# MAX-M8_Breakout.net
KiCad netlist of a schematic drawn in EAGLE
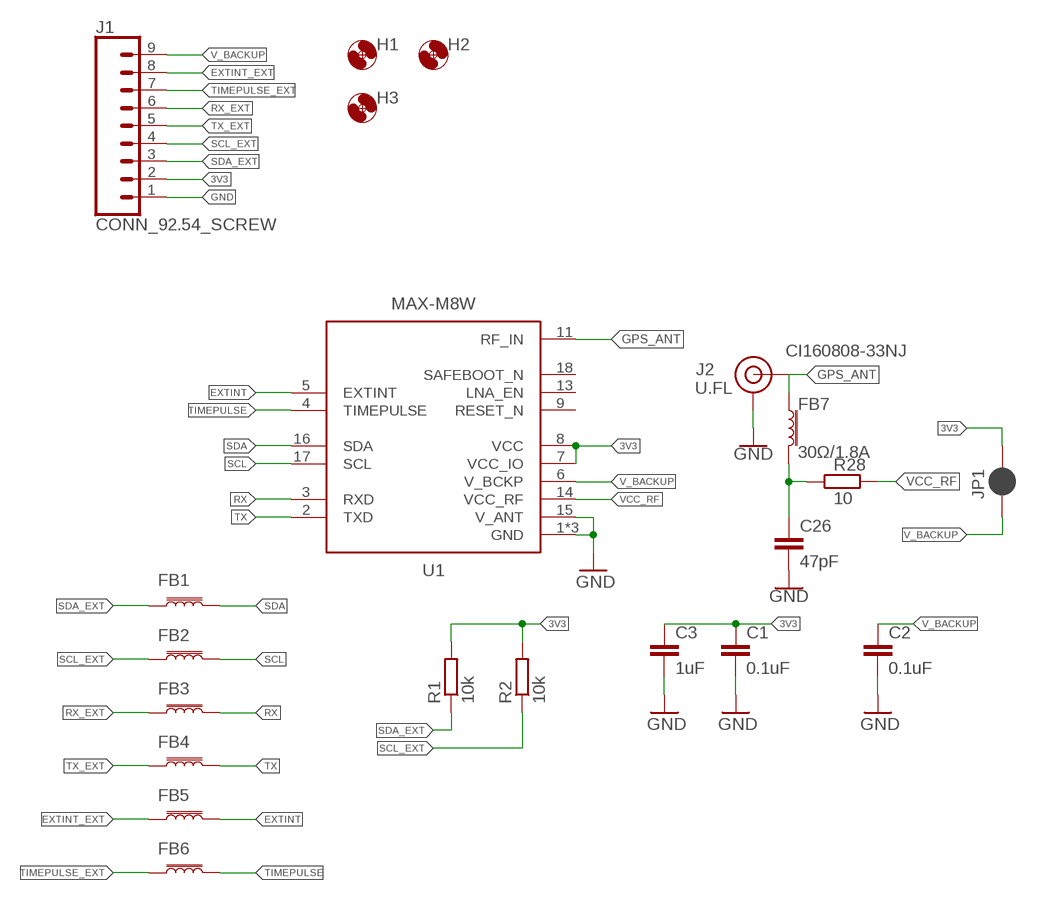
[diagram p0: schematic, sheet 1]

(export (version "E")
  (design (tool "Eeschema 10.0.6"))
  (components
    (comp (ref "C1")
      (value "0.1uF")
      (footprint "eagle-import:C0603")
      (fields (field (name "MF") "Murata") (field (name "MPN") "GCM188R71E104KA57D"))
      (libsource (lib "eagle-import") (part "C-EUC06030.1UF"))
    )
    (comp (ref "C2")
      (value "0.1uF")
      (footprint "eagle-import:C0603")
      (fields (field (name "MF") "Murata") (field (name "MPN") "GCM188R71E104KA57D"))
      (libsource (lib "eagle-import") (part "C-EUC06030.1UF"))
    )
    (comp (ref "C3")
      (value "1uF")
      (footprint "eagle-import:C0603")
      (fields (field (name "MF") "Yaiyo Yuden") (field (name "MPN") "EMK107BJ105KA-T"))
      (libsource (lib "eagle-import") (part "C-EUC06031UF"))
    )
    (comp (ref "C26")
      (value "47pF")
      (footprint "eagle-import:C0402")
      (libsource (lib "eagle-import") (part "C-EUC0402"))
    )
    (comp (ref "FB1")
      (value "FERRITE_BEAD1KS0402")
      (footprint "eagle-import:R0402")
      (fields (field (name "MF") "Murata") (field (name "MPN") "BLM15HD102SN1D"))
      (libsource (lib "eagle-import") (part "FERRITE_BEAD04021KS"))
    )
    (comp (ref "FB2")
      (value "FERRITE_BEAD1KS0402")
      (footprint "eagle-import:R0402")
      (fields (field (name "MF") "Murata") (field (name "MPN") "BLM15HD102SN1D"))
      (libsource (lib "eagle-import") (part "FERRITE_BEAD04021KS"))
    )
    (comp (ref "FB3")
      (value "FERRITE_BEAD1KS0402")
      (footprint "eagle-import:R0402")
      (fields (field (name "MF") "Murata") (field (name "MPN") "BLM15HD102SN1D"))
      (libsource (lib "eagle-import") (part "FERRITE_BEAD04021KS"))
    )
    (comp (ref "FB4")
      (value "FERRITE_BEAD1KS0402")
      (footprint "eagle-import:R0402")
      (fields (field (name "MF") "Murata") (field (name "MPN") "BLM15HD102SN1D"))
      (libsource (lib "eagle-import") (part "FERRITE_BEAD04021KS"))
    )
    (comp (ref "FB5")
      (value "FERRITE_BEAD1KS0402")
      (footprint "eagle-import:R0402")
      (fields (field (name "MF") "Murata") (field (name "MPN") "BLM15HD102SN1D"))
      (libsource (lib "eagle-import") (part "FERRITE_BEAD04021KS"))
    )
    (comp (ref "FB6")
      (value "FERRITE_BEAD1KS0402")
      (footprint "eagle-import:R0402")
      (fields (field (name "MF") "Murata") (field (name "MPN") "BLM15HD102SN1D"))
      (libsource (lib "eagle-import") (part "FERRITE_BEAD04021KS"))
    )
    (comp (ref "FB7")
      (value "30Ω/1.8A")
      (footprint "eagle-import:0603")
      (fields (field (name "MF") "TDK") (field (name "MPN") "MPZ1608D300BTA00"))
      (libsource (lib "eagle-import") (part "FERRITE_BEAD-0603"))
    )
    (comp (ref "H1")
      (value "MOUNTING_HOLE2_NP")
      (footprint "eagle-import:2_56")
      (fields (field (name "MPN") "DNP"))
      (libsource (lib "eagle-import") (part "MOUNTING_HOLE2_NP"))
    )
    (comp (ref "H2")
      (value "MOUNTING_HOLE2_NP")
      (footprint "eagle-import:2_56")
      (fields (field (name "MPN") "DNP"))
      (libsource (lib "eagle-import") (part "MOUNTING_HOLE2_NP"))
    )
    (comp (ref "H3")
      (value "MOUNTING_HOLE2_NP")
      (footprint "eagle-import:2_56")
      (fields (field (name "MPN") "DNP"))
      (libsource (lib "eagle-import") (part "MOUNTING_HOLE2_NP"))
    )
    (comp (ref "J1")
      (value "CONN_92.54_SCREW")
      (footprint "eagle-import:1X09_SCREW")
      (fields (field (name "MF") "TE") (field (name "MPN") "282834-9"))
      (libsource (lib "eagle-import") (part "CONN_92.54_SCREW"))
    )
    (comp (ref "J2")
      (value "U.FL")
      (footprint "eagle-import:U.FL")
      (fields (field (name "MF") "Molex") (field (name "MPN") "0734120110"))
      (libsource (lib "eagle-import") (part "U.FL2PIN"))
    )
    (comp (ref "JP1")
      (value "JUMPER-SMT_2_NC_PASTE_SILK")
      (footprint "eagle-import:SMT-JUMPER_2_NC_PASTE_SILK")
      (libsource (lib "eagle-import") (part "JUMPER-SMT_2_NC_PASTE_SILK"))
    )
    (comp (ref "R1")
      (value "10k")
      (footprint "eagle-import:R0603")
      (fields (field (name "MF") "Yageo") (field (name "MPN") "RC0603FR-0710KL"))
      (libsource (lib "eagle-import") (part "R-EU_R060310K"))
    )
    (comp (ref "R2")
      (value "10k")
      (footprint "eagle-import:R0603")
      (fields (field (name "MF") "Yageo") (field (name "MPN") "RC0603FR-0710KL"))
      (libsource (lib "eagle-import") (part "R-EU_R060310K"))
    )
    (comp (ref "R28")
      (value "10")
      (footprint "eagle-import:R0402")
      (fields (field (name "MF") "Yageo"))
      (libsource (lib "eagle-import") (part "R-EU_R0402"))
    )
    (comp (ref "U1")
      (value "MAX-M8W")
      (footprint "eagle-import:MAX-M8")
      (fields (field (name "DISP") "MAX-M8W") (field (name "MF") "U-Blox") (field (name "MPN") "MAX-M8W-0"))
      (libsource (lib "eagle-import") (part "MAX-M8W"))
    )
  )
  (nets
    (net (code "1") (name "3V3") (class "Default")
      (node (ref "C1") (pin "1") (pinfunction "1_1") (pintype "passive"))
      (node (ref "C3") (pin "1") (pinfunction "1_1") (pintype "passive"))
      (node (ref "J1") (pin "2") (pinfunction "2_2") (pintype "passive"))
      (node (ref "JP1") (pin "2") (pinfunction "2_2") (pintype "passive"))
      (node (ref "R1") (pin "2") (pinfunction "2_2") (pintype "passive"))
      (node (ref "R2") (pin "2") (pinfunction "2_2") (pintype "passive"))
      (node (ref "U1") (pin "7") (pinfunction "VCC_IO_7") (pintype "power_in"))
      (node (ref "U1") (pin "8") (pinfunction "VCC_8") (pintype "power_in"))
    )
    (net (code "2") (name "EXTINT") (class "Default")
      (node (ref "FB5") (pin "2") (pinfunction "2_2") (pintype "passive"))
      (node (ref "U1") (pin "5") (pinfunction "EXTINT_5") (pintype "bidirectional"))
    )
    (net (code "3") (name "EXTINT_EXT") (class "Default")
      (node (ref "FB5") (pin "1") (pinfunction "1_1") (pintype "passive"))
      (node (ref "J1") (pin "8") (pinfunction "8_8") (pintype "passive"))
    )
    (net (code "4") (name "GND") (class "Default")
      (node (ref "C1") (pin "2") (pinfunction "2_2") (pintype "passive"))
      (node (ref "C2") (pin "2") (pinfunction "2_2") (pintype "passive"))
      (node (ref "C26") (pin "2") (pinfunction "2_2") (pintype "passive"))
      (node (ref "C3") (pin "2") (pinfunction "2_2") (pintype "passive"))
      (node (ref "J1") (pin "1") (pinfunction "1_1") (pintype "passive"))
      (node (ref "J2") (pin "1") (pinfunction "GND_1") (pintype "bidirectional"))
      (node (ref "J2") (pin "2") (pinfunction "GND_2") (pintype "bidirectional"))
      (node (ref "U1") (pin "1") (pinfunction "GND_1") (pintype "power_in"))
      (node (ref "U1") (pin "10") (pinfunction "GND_10") (pintype "power_in"))
      (node (ref "U1") (pin "12") (pinfunction "GND_12") (pintype "power_in"))
      (node (ref "U1") (pin "15") (pinfunction "V_ANT_15") (pintype "power_in"))
    )
    (net (code "5") (name "GPS_ANT") (class "Default")
      (node (ref "FB7") (pin "1") (pinfunction "1_1") (pintype "passive"))
      (node (ref "J2") (pin "FEED") (pinfunction "SIGNAL_FEED") (pintype "bidirectional"))
      (node (ref "U1") (pin "11") (pinfunction "RF_IN_11") (pintype "input"))
    )
    (net (code "6") (name "Net-(C26-Pad1)") (class "Default")
      (node (ref "C26") (pin "1") (pinfunction "1_1") (pintype "passive"))
      (node (ref "FB7") (pin "2") (pinfunction "2_2") (pintype "passive"))
      (node (ref "R28") (pin "1") (pinfunction "1_1") (pintype "passive"))
    )
    (net (code "7") (name "RX") (class "Default")
      (node (ref "FB3") (pin "2") (pinfunction "2_2") (pintype "passive"))
      (node (ref "U1") (pin "3") (pinfunction "RXD_3") (pintype "input"))
    )
    (net (code "8") (name "RX_EXT") (class "Default")
      (node (ref "FB3") (pin "1") (pinfunction "1_1") (pintype "passive"))
      (node (ref "J1") (pin "6") (pinfunction "6_6") (pintype "passive"))
    )
    (net (code "9") (name "SCL") (class "Default")
      (node (ref "FB2") (pin "2") (pinfunction "2_2") (pintype "passive"))
      (node (ref "U1") (pin "17") (pinfunction "SCL_17") (pintype "input"))
    )
    (net (code "10") (name "SCL_EXT") (class "Default")
      (node (ref "FB2") (pin "1") (pinfunction "1_1") (pintype "passive"))
      (node (ref "J1") (pin "4") (pinfunction "4_4") (pintype "passive"))
      (node (ref "R2") (pin "1") (pinfunction "1_1") (pintype "passive"))
    )
    (net (code "11") (name "SDA") (class "Default")
      (node (ref "FB1") (pin "2") (pinfunction "2_2") (pintype "passive"))
      (node (ref "U1") (pin "16") (pinfunction "SDA_16") (pintype "bidirectional"))
    )
    (net (code "12") (name "SDA_EXT") (class "Default")
      (node (ref "FB1") (pin "1") (pinfunction "1_1") (pintype "passive"))
      (node (ref "J1") (pin "3") (pinfunction "3_3") (pintype "passive"))
      (node (ref "R1") (pin "1") (pinfunction "1_1") (pintype "passive"))
    )
    (net (code "13") (name "TIMEPULSE") (class "Default")
      (node (ref "FB6") (pin "2") (pinfunction "2_2") (pintype "passive"))
      (node (ref "U1") (pin "4") (pinfunction "TIMEPULSE_4") (pintype "output"))
    )
    (net (code "14") (name "TIMEPULSE_EXT") (class "Default")
      (node (ref "FB6") (pin "1") (pinfunction "1_1") (pintype "passive"))
      (node (ref "J1") (pin "7") (pinfunction "7_7") (pintype "passive"))
    )
    (net (code "15") (name "TX") (class "Default")
      (node (ref "FB4") (pin "2") (pinfunction "2_2") (pintype "passive"))
      (node (ref "U1") (pin "2") (pinfunction "TXD_2") (pintype "bidirectional"))
    )
    (net (code "16") (name "TX_EXT") (class "Default")
      (node (ref "FB4") (pin "1") (pinfunction "1_1") (pintype "passive"))
      (node (ref "J1") (pin "5") (pinfunction "5_5") (pintype "passive"))
    )
    (net (code "17") (name "VCC_RF") (class "Default")
      (node (ref "R28") (pin "2") (pinfunction "2_2") (pintype "passive"))
      (node (ref "U1") (pin "14") (pinfunction "VCC_RF_14") (pintype "power_in"))
    )
    (net (code "18") (name "V_BACKUP") (class "Default")
      (node (ref "C2") (pin "1") (pinfunction "1_1") (pintype "passive"))
      (node (ref "J1") (pin "9") (pinfunction "9_9") (pintype "passive"))
      (node (ref "JP1") (pin "1") (pinfunction "1_1") (pintype "passive"))
      (node (ref "U1") (pin "6") (pinfunction "V_BCKP_6") (pintype "power_in"))
    )
    (net (code "19") (name "unconnected-(U1-LNA_EN-Pad13)") (class "Default")
      (node (ref "U1") (pin "13") (pinfunction "LNA_EN_13") (pintype "bidirectional"))
    )
    (net (code "20") (name "unconnected-(U1-RESET_N-Pad9)") (class "Default")
      (node (ref "U1") (pin "9") (pinfunction "RESET_N_9") (pintype "input"))
    )
    (net (code "21") (name "unconnected-(U1-SAFEBOOT_N-Pad18)") (class "Default")
      (node (ref "U1") (pin "18") (pinfunction "SAFEBOOT_N_18") (pintype "input"))
    )
  )
)
